# ATTinyServoSMT_v10.net
KiCad netlist of a schematic drawn in EAGLE
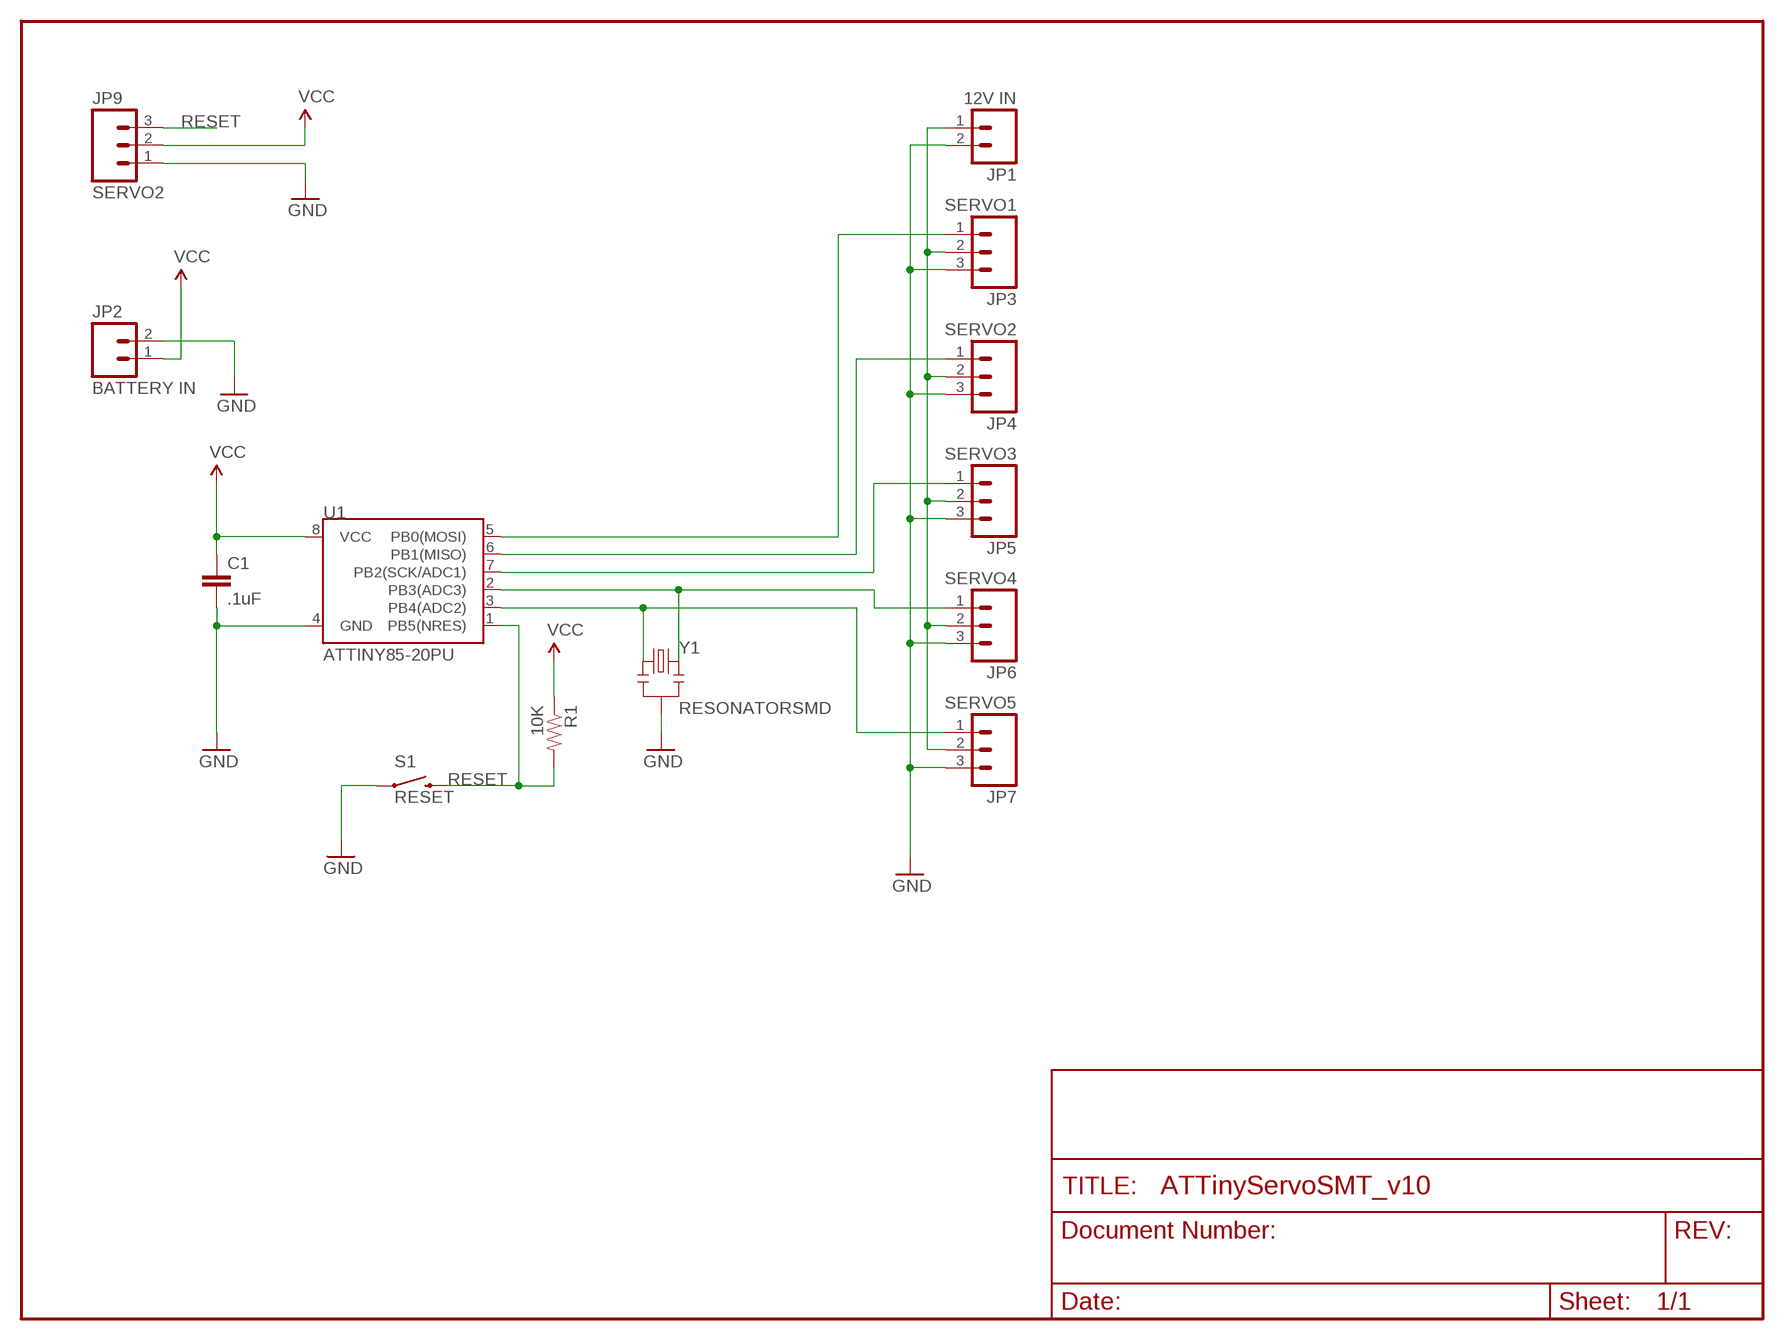
[diagram p0: schematic, sheet 1]

(export (version "E")
  (design (tool "Eeschema 10.0.6"))
  (components
    (comp (ref "C1")
      (value ".1uF")
      (footprint "eagle-import:0603-CAP")
      (libsource (lib "eagle-import") (part "CAP0603-CAP"))
    )
    (comp (ref "JP1")
      (value "12V IN")
      (footprint "eagle-import:SCREWTERMINAL-3.5MM-2")
      (libsource (lib "eagle-import") (part "M023.5MM"))
    )
    (comp (ref "JP2")
      (value "BATTERY IN")
      (footprint "eagle-import:SCREWTERMINAL-3.5MM-2")
      (libsource (lib "eagle-import") (part "M023.5MM"))
    )
    (comp (ref "JP3")
      (value "SERVO1")
      (footprint "eagle-import:1X03")
      (libsource (lib "eagle-import") (part "M03PTH"))
    )
    (comp (ref "JP4")
      (value "SERVO2")
      (footprint "eagle-import:1X03")
      (libsource (lib "eagle-import") (part "M03PTH"))
    )
    (comp (ref "JP5")
      (value "SERVO3")
      (footprint "eagle-import:1X03")
      (libsource (lib "eagle-import") (part "M03PTH"))
    )
    (comp (ref "JP6")
      (value "SERVO4")
      (footprint "eagle-import:1X03")
      (libsource (lib "eagle-import") (part "M03PTH"))
    )
    (comp (ref "JP7")
      (value "SERVO5")
      (footprint "eagle-import:1X03")
      (libsource (lib "eagle-import") (part "M03PTH"))
    )
    (comp (ref "JP9")
      (value "SERVO2")
      (footprint "eagle-import:1X03")
      (libsource (lib "eagle-import") (part "M03PTH"))
    )
    (comp (ref "R1")
      (value "10K")
      (footprint "eagle-import:0603-RES")
      (libsource (lib "eagle-import") (part "RESISTOR0603-RES"))
    )
    (comp (ref "S1")
      (value "RESET")
      (footprint "eagle-import:TACTILE_SWITCH_SMD")
      (libsource (lib "eagle-import") (part "SWITCH-MOMENTARY-2SMD"))
    )
    (comp (ref "U1")
      (value "ATTINY85-20PU")
      (footprint "eagle-import:SO08-EIAJ")
      (libsource (lib "eagle-import") (part "ATTINY45"))
    )
    (comp (ref "Y1")
      (value "RESONATORSMD")
      (footprint "eagle-import:RESONATOR-SMD")
      (libsource (lib "eagle-import") (part "RESONATORSMD"))
    )
  )
  (nets
    (net (code "1") (name "/RESET") (class "Default")
      (node (ref "JP9") (pin "3") (pinfunction "3_3") (pintype "passive"))
      (node (ref "R1") (pin "2") (pinfunction "2_2") (pintype "passive"))
      (node (ref "S1") (pin "3") (pinfunction "2_3") (pintype "passive"))
      (node (ref "U1") (pin "1") (pinfunction "PB5(NRES)_1") (pintype "bidirectional"))
    )
    (net (code "2") (name "GND") (class "Default")
      (node (ref "C1") (pin "2") (pinfunction "2_2") (pintype "passive"))
      (node (ref "JP1") (pin "2") (pinfunction "2_2") (pintype "passive"))
      (node (ref "JP2") (pin "2") (pinfunction "2_2") (pintype "passive"))
      (node (ref "JP3") (pin "3") (pinfunction "3_3") (pintype "passive"))
      (node (ref "JP4") (pin "3") (pinfunction "3_3") (pintype "passive"))
      (node (ref "JP5") (pin "3") (pinfunction "3_3") (pintype "passive"))
      (node (ref "JP6") (pin "3") (pinfunction "3_3") (pintype "passive"))
      (node (ref "JP7") (pin "3") (pinfunction "3_3") (pintype "passive"))
      (node (ref "JP9") (pin "1") (pinfunction "1_1") (pintype "passive"))
      (node (ref "S1") (pin "1") (pinfunction "1_1") (pintype "passive"))
      (node (ref "U1") (pin "4") (pinfunction "GND_4") (pintype "bidirectional"))
      (node (ref "Y1") (pin "2") (pinfunction "2_2") (pintype "passive"))
    )
    (net (code "3") (name "Net-(JP1-Pad1)") (class "Default")
      (node (ref "JP1") (pin "1") (pinfunction "1_1") (pintype "passive"))
      (node (ref "JP3") (pin "2") (pinfunction "2_2") (pintype "passive"))
      (node (ref "JP4") (pin "2") (pinfunction "2_2") (pintype "passive"))
      (node (ref "JP5") (pin "2") (pinfunction "2_2") (pintype "passive"))
      (node (ref "JP6") (pin "2") (pinfunction "2_2") (pintype "passive"))
      (node (ref "JP7") (pin "2") (pinfunction "2_2") (pintype "passive"))
    )
    (net (code "4") (name "Net-(U1-PB0(MOSI))") (class "Default")
      (node (ref "JP3") (pin "1") (pinfunction "1_1") (pintype "passive"))
      (node (ref "U1") (pin "5") (pinfunction "PB0(MOSI)_5") (pintype "bidirectional"))
    )
    (net (code "5") (name "Net-(U1-PB1(MISO))") (class "Default")
      (node (ref "JP4") (pin "1") (pinfunction "1_1") (pintype "passive"))
      (node (ref "U1") (pin "6") (pinfunction "PB1(MISO)_6") (pintype "bidirectional"))
    )
    (net (code "6") (name "Net-(U1-PB2(SCK{slash}ADC1))") (class "Default")
      (node (ref "JP5") (pin "1") (pinfunction "1_1") (pintype "passive"))
      (node (ref "U1") (pin "7") (pinfunction "PB2(SCK/ADC1)_7") (pintype "bidirectional"))
    )
    (net (code "7") (name "Net-(U1-PB3(ADC3))") (class "Default")
      (node (ref "JP6") (pin "1") (pinfunction "1_1") (pintype "passive"))
      (node (ref "U1") (pin "2") (pinfunction "PB3(ADC3)_2") (pintype "bidirectional"))
      (node (ref "Y1") (pin "3") (pinfunction "3_3") (pintype "passive"))
    )
    (net (code "8") (name "Net-(U1-PB4(ADC2))") (class "Default")
      (node (ref "JP7") (pin "1") (pinfunction "1_1") (pintype "passive"))
      (node (ref "U1") (pin "3") (pinfunction "PB4(ADC2)_3") (pintype "bidirectional"))
      (node (ref "Y1") (pin "1") (pinfunction "1_1") (pintype "passive"))
    )
    (net (code "9") (name "VCC") (class "Default")
      (node (ref "C1") (pin "1") (pinfunction "1_1") (pintype "passive"))
      (node (ref "JP2") (pin "1") (pinfunction "1_1") (pintype "passive"))
      (node (ref "JP9") (pin "2") (pinfunction "2_2") (pintype "passive"))
      (node (ref "R1") (pin "1") (pinfunction "1_1") (pintype "passive"))
      (node (ref "U1") (pin "8") (pinfunction "VCC_8") (pintype "bidirectional"))
    )
  )
)
